# KNX_POE.net
KiCad netlist of a schematic drawn in Altium Designer
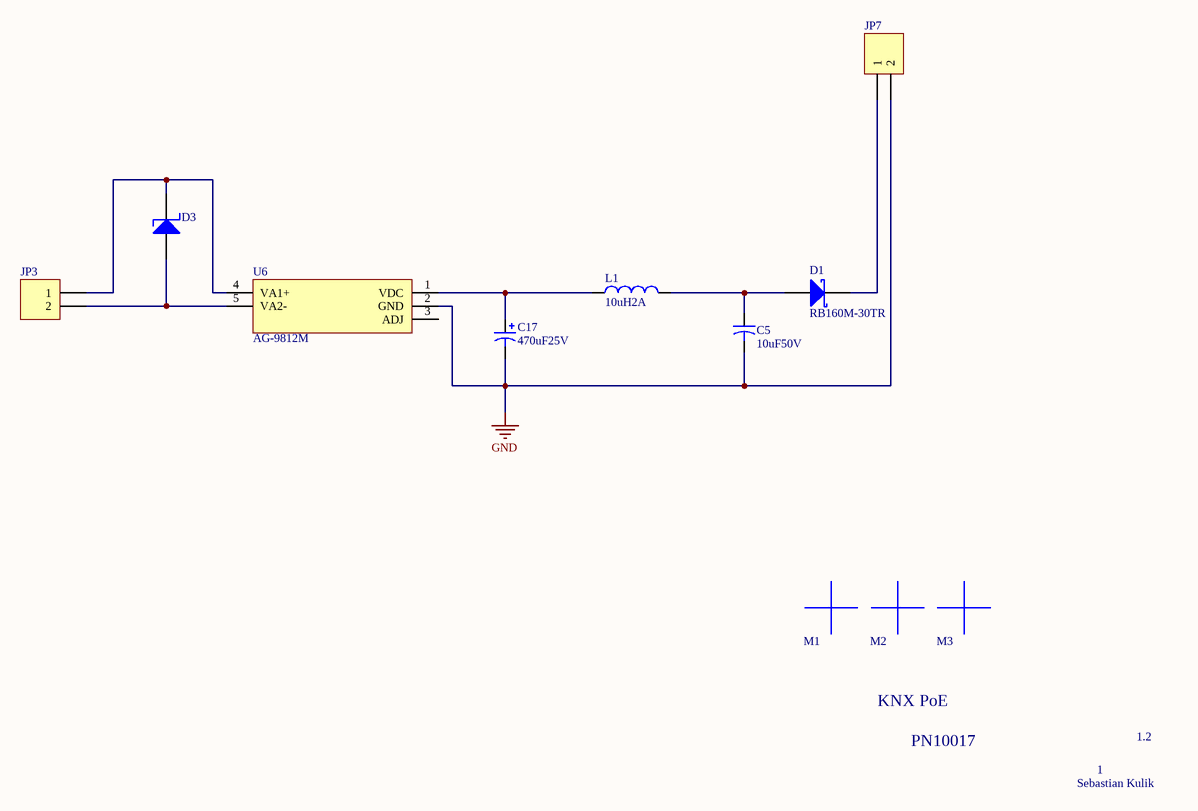
[diagram p0: KNX_POE.SchDoc]

(export (version "E")
  (design (tool "Eeschema 10.0.6"))
  (components
    (comp (ref "C5")
      (value "10uF50V")
      (footprint "C1210")
      (description "AVX,  X7R, 10%, 50V")
      (fields
        (field (name "MANUFACTURER") "AVX")
        (field (name "Comment") "10uF50V_1210")
        (field (name "PUBLISHER") "Sebastian Kulik")
      )
      (libsource (lib "Capacitors") (part "10uF50V_1210"))
    )
    (comp (ref "C17")
      (value "470uF25V")
      (footprint "Panasonic-H13")
      (description "Panasonic, TG series")
      (fields
        (field (name "MANUFACTURER") "Panasonic")
        (field (name "Comment") "470uF25V_POL")
        (field (name "PUBLISHER") "Sebastian Kulik")
      )
      (libsource (lib "Capacitors") (part "470uF25V_POL"))
    )
    (comp (ref "D1")
      (value "RB160M-30TR")
      (footprint "SOD123")
      (description "Diode Schottky,2A,40V")
      (fields (field (name "MANUFACTURER") "Rohm") (field (name "PUBLISHER") "Sebastian Kulik"))
      (libsource (lib "Discrete") (part "RB160M-30TR"))
    )
    (comp (ref "D3")
      (value "SMAJ58A-E3/61")
      (footprint "DO214A")
      (description "TVS, 400W, 58V")
      (fields (field (name "MANUFACTURER") "Vishay") (field (name "PUBLISHER") "Sebastian Kulik"))
      (libsource (lib "Discrete") (part "SMAJ58A-E3/61"))
    )
    (comp (ref "JP3")
      (value "Plug_2_90_2.54")
      (footprint "HDR1X2-down")
      (description "Plug, 2-Pin")
      (fields (field (name "MANUFACTURER") "WE") (field (name "PUBLISHER") "Sebastian Kulik"))
      (libsource (lib "") (part "Plug_2_90_2.54_1"))
    )
    (comp (ref "JP7")
      (value "Plug_2_90_2.54")
      (footprint "HDR1X2-down")
      (description "Plug, 2-Pin")
      (fields (field (name "MANUFACTURER") "WE") (field (name "PUBLISHER") "Sebastian Kulik"))
      (libsource (lib "Connectors") (part "Plug_2_90_2.54"))
    )
    (comp (ref "L1")
      (value "10uH2A")
      (footprint "WE-PD2_1")
      (description "WE-PD2, 10uH2A")
      (fields (field (name "MANUFACTURER") "WE") (field (name "PUBLISHER") "Sebastian Kulik"))
      (libsource (lib "Passives") (part "10uH2A_WE-PD2"))
    )
    (comp (ref "M1") (value "Mark") (footprint "Mark-3mm") (libsource (lib "Symbols") (part "Mark")))
    (comp (ref "M2") (value "Mark") (footprint "Mark-3mm") (libsource (lib "Symbols") (part "Mark")))
    (comp (ref "M3") (value "Mark") (footprint "Mark-3mm") (libsource (lib "Symbols") (part "Mark")))
    (comp (ref "U6")
      (value "AG-9812M")
      (footprint "Ag9812M")
      (description "PoE, 12V")
      (fields (field (name "MANUFACTURER") "Silvertel") (field (name "PUBLISHER") "Sebastian Kulik"))
      (libsource (lib "ICs") (part "AG-9812M"))
    )
  )
  (nets
    (net (code "1") (name "GND") (class "Default")
      (node (ref "C17") (pin "2") (pinfunction "2_2") (pintype "passive"))
      (node (ref "C5") (pin "2") (pinfunction "2_2") (pintype "passive"))
      (node (ref "JP7") (pin "2") (pinfunction "2_2") (pintype "passive"))
      (node (ref "U6") (pin "2") (pinfunction "GND_2") (pintype "passive"))
    )
    (net (code "2") (name "Net-(D1-A)") (class "Default")
      (node (ref "C5") (pin "1") (pinfunction "1_1") (pintype "passive"))
      (node (ref "D1") (pin "2") (pinfunction "A_2") (pintype "passive"))
      (node (ref "L1") (pin "2") (pinfunction "2_2") (pintype "passive"))
    )
    (net (code "3") (name "Net-(D1-K)") (class "Default")
      (node (ref "D1") (pin "1") (pinfunction "K_1") (pintype "passive"))
      (node (ref "JP7") (pin "1") (pinfunction "1_1") (pintype "passive"))
    )
    (net (code "4") (name "Net-(D3-A)") (class "Default")
      (node (ref "D3") (pin "2") (pinfunction "A_2") (pintype "passive"))
      (node (ref "JP3") (pin "2") (pinfunction "2_2") (pintype "passive"))
      (node (ref "U6") (pin "5") (pinfunction "VA2-_5") (pintype "passive"))
    )
    (net (code "5") (name "Net-(D3-K)") (class "Default")
      (node (ref "D3") (pin "1") (pinfunction "K_1") (pintype "passive"))
      (node (ref "JP3") (pin "1") (pinfunction "1_1") (pintype "passive"))
      (node (ref "U6") (pin "4") (pinfunction "VA1+_4") (pintype "passive"))
    )
    (net (code "6") (name "Net-(U6-VDC)") (class "Default")
      (node (ref "C17") (pin "1") (pinfunction "1_1") (pintype "passive"))
      (node (ref "L1") (pin "1") (pinfunction "1_1") (pintype "passive"))
      (node (ref "U6") (pin "1") (pinfunction "VDC_1") (pintype "power_in"))
    )
    (net (code "7") (name "unconnected-(U6-ADJ-Pad3)") (class "Default")
      (node (ref "U6") (pin "3") (pinfunction "ADJ_3") (pintype "passive"))
    )
  )
)
